# hw2.net
KiCad netlist of a schematic drawn in EAGLE
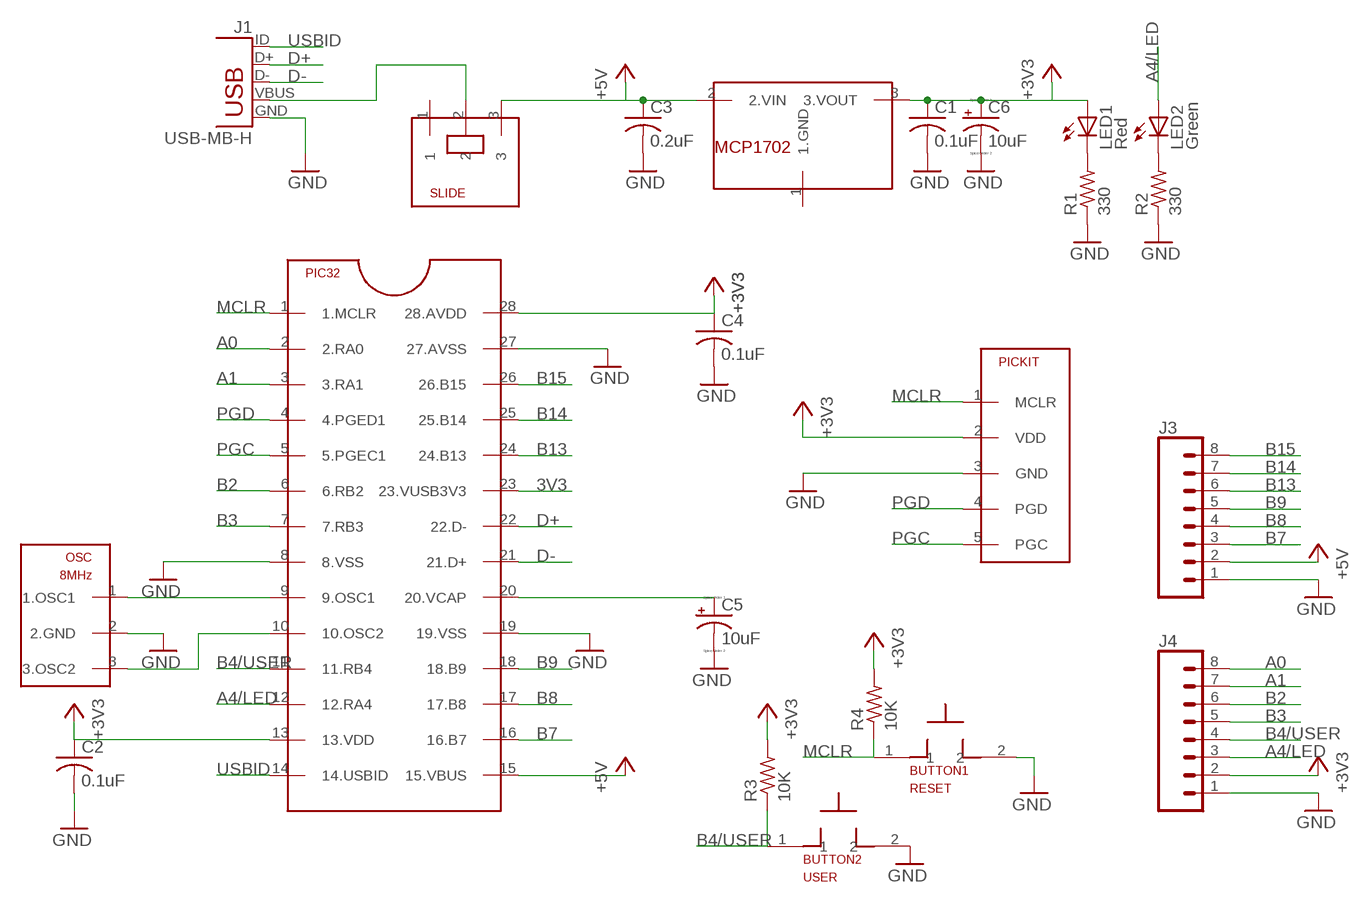
[diagram p0: schematic, sheet 1]

(export (version "E")
  (design (tool "Eeschema 10.0.6"))
  (components
    (comp (ref "BUTTON1")
      (value "RESET")
      (footprint "eagle-import:PB")
      (libsource (lib "eagle-import") (part "PB"))
    )
    (comp (ref "BUTTON2")
      (value "USER")
      (footprint "eagle-import:PB")
      (libsource (lib "eagle-import") (part "PB"))
    )
    (comp (ref "C1")
      (value "0.1uF")
      (footprint "eagle-import:C025-025X050")
      (libsource (lib "eagle-import") (part "C-US025-025X050"))
    )
    (comp (ref "C2")
      (value "0.1uF")
      (footprint "eagle-import:C025-025X050")
      (libsource (lib "eagle-import") (part "C-US025-025X050"))
    )
    (comp (ref "C3")
      (value "0.2uF")
      (footprint "eagle-import:C025-025X050")
      (libsource (lib "eagle-import") (part "C-US025-025X050"))
    )
    (comp (ref "C4")
      (value "0.1uF")
      (footprint "eagle-import:C025-025X050")
      (libsource (lib "eagle-import") (part "C-US025-025X050"))
    )
    (comp (ref "C5")
      (value "10uF")
      (footprint "eagle-import:B45181B")
      (libsource (lib "eagle-import") (part "CPOL-USB45181B"))
    )
    (comp (ref "C6")
      (value "10uF")
      (footprint "eagle-import:B45181B")
      (libsource (lib "eagle-import") (part "CPOL-USB45181B"))
    )
    (comp (ref "J1")
      (value "USB-MB-H")
      (footprint "eagle-import:USB-MB-H")
      (libsource (lib "eagle-import") (part "USB-MB-H"))
    )
    (comp (ref "J3")
      (value "CONN_08_01")
      (footprint "eagle-import:1X08")
      (libsource (lib "eagle-import") (part "CONN_08_01"))
    )
    (comp (ref "J4")
      (value "CONN_08_01")
      (footprint "eagle-import:1X08")
      (libsource (lib "eagle-import") (part "CONN_08_01"))
    )
    (comp (ref "LED1")
      (value "Red")
      (footprint "eagle-import:LED3MM")
      (libsource (lib "eagle-import") (part "LED3MM"))
    )
    (comp (ref "LED2")
      (value "Green")
      (footprint "eagle-import:LED3MM")
      (libsource (lib "eagle-import") (part "LED3MM"))
    )
    (comp (ref "MCP1702")
      (value "MCP1702")
      (footprint "eagle-import:TO92")
      (libsource (lib "eagle-import") (part "MCP1702"))
    )
    (comp (ref "OSC")
      (value "8MHz")
      (footprint "eagle-import:OSC")
      (libsource (lib "eagle-import") (part "OSC"))
    )
    (comp (ref "PIC32")
      (value "PIC32")
      (footprint "eagle-import:DIL28-3")
      (libsource (lib "eagle-import") (part "PIC32"))
    )
    (comp (ref "PICKIT")
      (value "PICKIT")
      (footprint "eagle-import:1X05")
      (libsource (lib "eagle-import") (part "PICKIT"))
    )
    (comp (ref "R1")
      (value "330")
      (footprint "eagle-import:0207_10")
      (libsource (lib "eagle-import") (part "R-US_0207/10"))
    )
    (comp (ref "R2")
      (value "330")
      (footprint "eagle-import:0207_10")
      (libsource (lib "eagle-import") (part "R-US_0207/10"))
    )
    (comp (ref "R3")
      (value "10K")
      (footprint "eagle-import:0207_10")
      (libsource (lib "eagle-import") (part "R-US_0207/10"))
    )
    (comp (ref "R4")
      (value "10K")
      (footprint "eagle-import:0207_10")
      (libsource (lib "eagle-import") (part "R-US_0207/10"))
    )
    (comp (ref "SLIDE")
      (value "SLIDE")
      (footprint "eagle-import:SLIDE")
      (libsource (lib "eagle-import") (part "SLIDE"))
    )
  )
  (nets
    (net (code "1") (name "+3V3") (class "Default")
      (node (ref "C1") (pin "1") (pinfunction "1_1") (pintype "passive"))
      (node (ref "C2") (pin "1") (pinfunction "1_1") (pintype "passive"))
      (node (ref "C4") (pin "1") (pinfunction "1_1") (pintype "passive"))
      (node (ref "C6") (pin "+") (pinfunction "+_+") (pintype "passive"))
      (node (ref "J4") (pin "2") (pinfunction "2_2") (pintype "passive"))
      (node (ref "LED1") (pin "A") (pinfunction "A_A") (pintype "passive"))
      (node (ref "MCP1702") (pin "3") (pinfunction "3.VOUT_3") (pintype "bidirectional"))
      (node (ref "PIC32") (pin "13") (pinfunction "13.VDD_13") (pintype "bidirectional"))
      (node (ref "PIC32") (pin "28") (pinfunction "28.AVDD_28") (pintype "bidirectional"))
      (node (ref "PICKIT") (pin "2") (pinfunction "VDD_2") (pintype "bidirectional"))
      (node (ref "R3") (pin "2") (pinfunction "2_2") (pintype "passive"))
      (node (ref "R4") (pin "2") (pinfunction "2_2") (pintype "passive"))
    )
    (net (code "2") (name "+5V") (class "Default")
      (node (ref "C3") (pin "1") (pinfunction "1_1") (pintype "passive"))
      (node (ref "J3") (pin "2") (pinfunction "2_2") (pintype "passive"))
      (node (ref "MCP1702") (pin "2") (pinfunction "2.VIN_2") (pintype "bidirectional"))
      (node (ref "PIC32") (pin "15") (pinfunction "15.VBUS_15") (pintype "bidirectional"))
      (node (ref "SLIDE") (pin "3") (pinfunction "3_3") (pintype "bidirectional"))
    )
    (net (code "3") (name "/3V3") (class "Default")
      (node (ref "PIC32") (pin "23") (pinfunction "23.VUSB3V3_23") (pintype "bidirectional"))
    )
    (net (code "4") (name "/A0") (class "Default")
      (node (ref "J4") (pin "8") (pinfunction "8_8") (pintype "passive"))
      (node (ref "PIC32") (pin "2") (pinfunction "2.RA0_2") (pintype "bidirectional"))
    )
    (net (code "5") (name "/A1") (class "Default")
      (node (ref "J4") (pin "7") (pinfunction "7_7") (pintype "passive"))
      (node (ref "PIC32") (pin "3") (pinfunction "3.RA1_3") (pintype "bidirectional"))
    )
    (net (code "6") (name "/A4{slash}LED") (class "Default")
      (node (ref "J4") (pin "3") (pinfunction "3_3") (pintype "passive"))
      (node (ref "LED2") (pin "A") (pinfunction "A_A") (pintype "passive"))
      (node (ref "PIC32") (pin "12") (pinfunction "12.RA4_12") (pintype "bidirectional"))
    )
    (net (code "7") (name "/B2") (class "Default")
      (node (ref "J4") (pin "6") (pinfunction "6_6") (pintype "passive"))
      (node (ref "PIC32") (pin "6") (pinfunction "6.RB2_6") (pintype "bidirectional"))
    )
    (net (code "8") (name "/B3") (class "Default")
      (node (ref "J4") (pin "5") (pinfunction "5_5") (pintype "passive"))
      (node (ref "PIC32") (pin "7") (pinfunction "7.RB3_7") (pintype "bidirectional"))
    )
    (net (code "9") (name "/B4{slash}USER") (class "Default")
      (node (ref "BUTTON2") (pin "1") (pinfunction "1_1") (pintype "bidirectional"))
      (node (ref "J4") (pin "4") (pinfunction "4_4") (pintype "passive"))
      (node (ref "PIC32") (pin "11") (pinfunction "11.RB4_11") (pintype "bidirectional"))
      (node (ref "R3") (pin "1") (pinfunction "1_1") (pintype "passive"))
    )
    (net (code "10") (name "/B7") (class "Default")
      (node (ref "J3") (pin "3") (pinfunction "3_3") (pintype "passive"))
      (node (ref "PIC32") (pin "16") (pinfunction "16.B7_16") (pintype "bidirectional"))
    )
    (net (code "11") (name "/B8") (class "Default")
      (node (ref "J3") (pin "4") (pinfunction "4_4") (pintype "passive"))
      (node (ref "PIC32") (pin "17") (pinfunction "17.B8_17") (pintype "bidirectional"))
    )
    (net (code "12") (name "/B9") (class "Default")
      (node (ref "J3") (pin "5") (pinfunction "5_5") (pintype "passive"))
      (node (ref "PIC32") (pin "18") (pinfunction "18.B9_18") (pintype "bidirectional"))
    )
    (net (code "13") (name "/B13") (class "Default")
      (node (ref "J3") (pin "6") (pinfunction "6_6") (pintype "passive"))
      (node (ref "PIC32") (pin "24") (pinfunction "24.B13_24") (pintype "bidirectional"))
    )
    (net (code "14") (name "/B14") (class "Default")
      (node (ref "J3") (pin "7") (pinfunction "7_7") (pintype "passive"))
      (node (ref "PIC32") (pin "25") (pinfunction "25.B14_25") (pintype "bidirectional"))
    )
    (net (code "15") (name "/B15") (class "Default")
      (node (ref "J3") (pin "8") (pinfunction "8_8") (pintype "passive"))
      (node (ref "PIC32") (pin "26") (pinfunction "26.B15_26") (pintype "bidirectional"))
    )
    (net (code "16") (name "/D+") (class "Default")
      (node (ref "J1") (pin "D+") (pinfunction "D+_D+") (pintype "bidirectional"))
      (node (ref "PIC32") (pin "22") (pinfunction "22.D-_22") (pintype "bidirectional"))
    )
    (net (code "17") (name "/D-") (class "Default")
      (node (ref "J1") (pin "D-") (pinfunction "D-_D-") (pintype "bidirectional"))
      (node (ref "PIC32") (pin "21") (pinfunction "21.D+_21") (pintype "bidirectional"))
    )
    (net (code "18") (name "/MCLR") (class "Default")
      (node (ref "BUTTON1") (pin "1") (pinfunction "1_1") (pintype "bidirectional"))
      (node (ref "PIC32") (pin "1") (pinfunction "1.MCLR_1") (pintype "bidirectional"))
      (node (ref "PICKIT") (pin "1") (pinfunction "MCLR_1") (pintype "bidirectional"))
      (node (ref "R4") (pin "1") (pinfunction "1_1") (pintype "passive"))
    )
    (net (code "19") (name "/PGC") (class "Default")
      (node (ref "PIC32") (pin "5") (pinfunction "5.PGEC1_5") (pintype "bidirectional"))
      (node (ref "PICKIT") (pin "5") (pinfunction "PGC_5") (pintype "bidirectional"))
    )
    (net (code "20") (name "/PGD") (class "Default")
      (node (ref "PIC32") (pin "4") (pinfunction "4.PGED1_4") (pintype "bidirectional"))
      (node (ref "PICKIT") (pin "4") (pinfunction "PGD_4") (pintype "bidirectional"))
    )
    (net (code "21") (name "/USBID") (class "Default")
      (node (ref "J1") (pin "ID") (pinfunction "ID_ID") (pintype "bidirectional"))
      (node (ref "PIC32") (pin "14") (pinfunction "14.USBID_14") (pintype "bidirectional"))
    )
    (net (code "22") (name "GND") (class "Default")
      (node (ref "BUTTON1") (pin "2") (pinfunction "2_2") (pintype "bidirectional"))
      (node (ref "BUTTON2") (pin "2") (pinfunction "2_2") (pintype "bidirectional"))
      (node (ref "C1") (pin "2") (pinfunction "2_2") (pintype "passive"))
      (node (ref "C2") (pin "2") (pinfunction "2_2") (pintype "passive"))
      (node (ref "C3") (pin "2") (pinfunction "2_2") (pintype "passive"))
      (node (ref "C4") (pin "2") (pinfunction "2_2") (pintype "passive"))
      (node (ref "C5") (pin "-") (pinfunction "-_-") (pintype "passive"))
      (node (ref "C6") (pin "-") (pinfunction "-_-") (pintype "passive"))
      (node (ref "J1") (pin "GND") (pinfunction "GND_GND") (pintype "bidirectional"))
      (node (ref "J3") (pin "1") (pinfunction "1_1") (pintype "passive"))
      (node (ref "J4") (pin "1") (pinfunction "1_1") (pintype "passive"))
      (node (ref "OSC") (pin "2") (pinfunction "2.GND_2") (pintype "bidirectional"))
      (node (ref "PIC32") (pin "19") (pinfunction "19.VSS_19") (pintype "bidirectional"))
      (node (ref "PIC32") (pin "27") (pinfunction "27.AVSS_27") (pintype "bidirectional"))
      (node (ref "PIC32") (pin "8") (pinfunction "8.VSS_8") (pintype "bidirectional"))
      (node (ref "PICKIT") (pin "3") (pinfunction "GND_3") (pintype "bidirectional"))
      (node (ref "R1") (pin "1") (pinfunction "1_1") (pintype "passive"))
      (node (ref "R2") (pin "1") (pinfunction "1_1") (pintype "passive"))
    )
    (net (code "23") (name "Net-(J1-PadVBUS)") (class "Default")
      (node (ref "J1") (pin "VBUS") (pinfunction "VBUS_VBUS") (pintype "bidirectional"))
      (node (ref "SLIDE") (pin "2") (pinfunction "2_2") (pintype "bidirectional"))
    )
    (net (code "24") (name "Net-(LED1-C)") (class "Default")
      (node (ref "LED1") (pin "K") (pinfunction "C_K") (pintype "passive"))
      (node (ref "R1") (pin "2") (pinfunction "2_2") (pintype "passive"))
    )
    (net (code "25") (name "Net-(LED2-C)") (class "Default")
      (node (ref "LED2") (pin "K") (pinfunction "C_K") (pintype "passive"))
      (node (ref "R2") (pin "2") (pinfunction "2_2") (pintype "passive"))
    )
    (net (code "26") (name "Net-(OSC-1.OSC1)") (class "Default")
      (node (ref "OSC") (pin "1") (pinfunction "1.OSC1_1") (pintype "bidirectional"))
      (node (ref "PIC32") (pin "9") (pinfunction "9.OSC1_9") (pintype "bidirectional"))
    )
    (net (code "27") (name "Net-(OSC-3.OSC2)") (class "Default")
      (node (ref "OSC") (pin "3") (pinfunction "3.OSC2_3") (pintype "bidirectional"))
      (node (ref "PIC32") (pin "10") (pinfunction "10.OSC2_10") (pintype "bidirectional"))
    )
    (net (code "28") (name "Net-(PIC32-20.VCAP)") (class "Default")
      (node (ref "C5") (pin "+") (pinfunction "+_+") (pintype "passive"))
      (node (ref "PIC32") (pin "20") (pinfunction "20.VCAP_20") (pintype "bidirectional"))
    )
    (net (code "29") (name "unconnected-(MCP1702-1.GND-Pad1)") (class "Default")
      (node (ref "MCP1702") (pin "1") (pinfunction "1.GND_1") (pintype "bidirectional"))
    )
    (net (code "30") (name "unconnected-(SLIDE-Pad1)") (class "Default")
      (node (ref "SLIDE") (pin "1") (pinfunction "1_1") (pintype "bidirectional"))
    )
  )
)
